# arrayboard_r0a.net
KiCad netlist of a schematic drawn in EAGLE
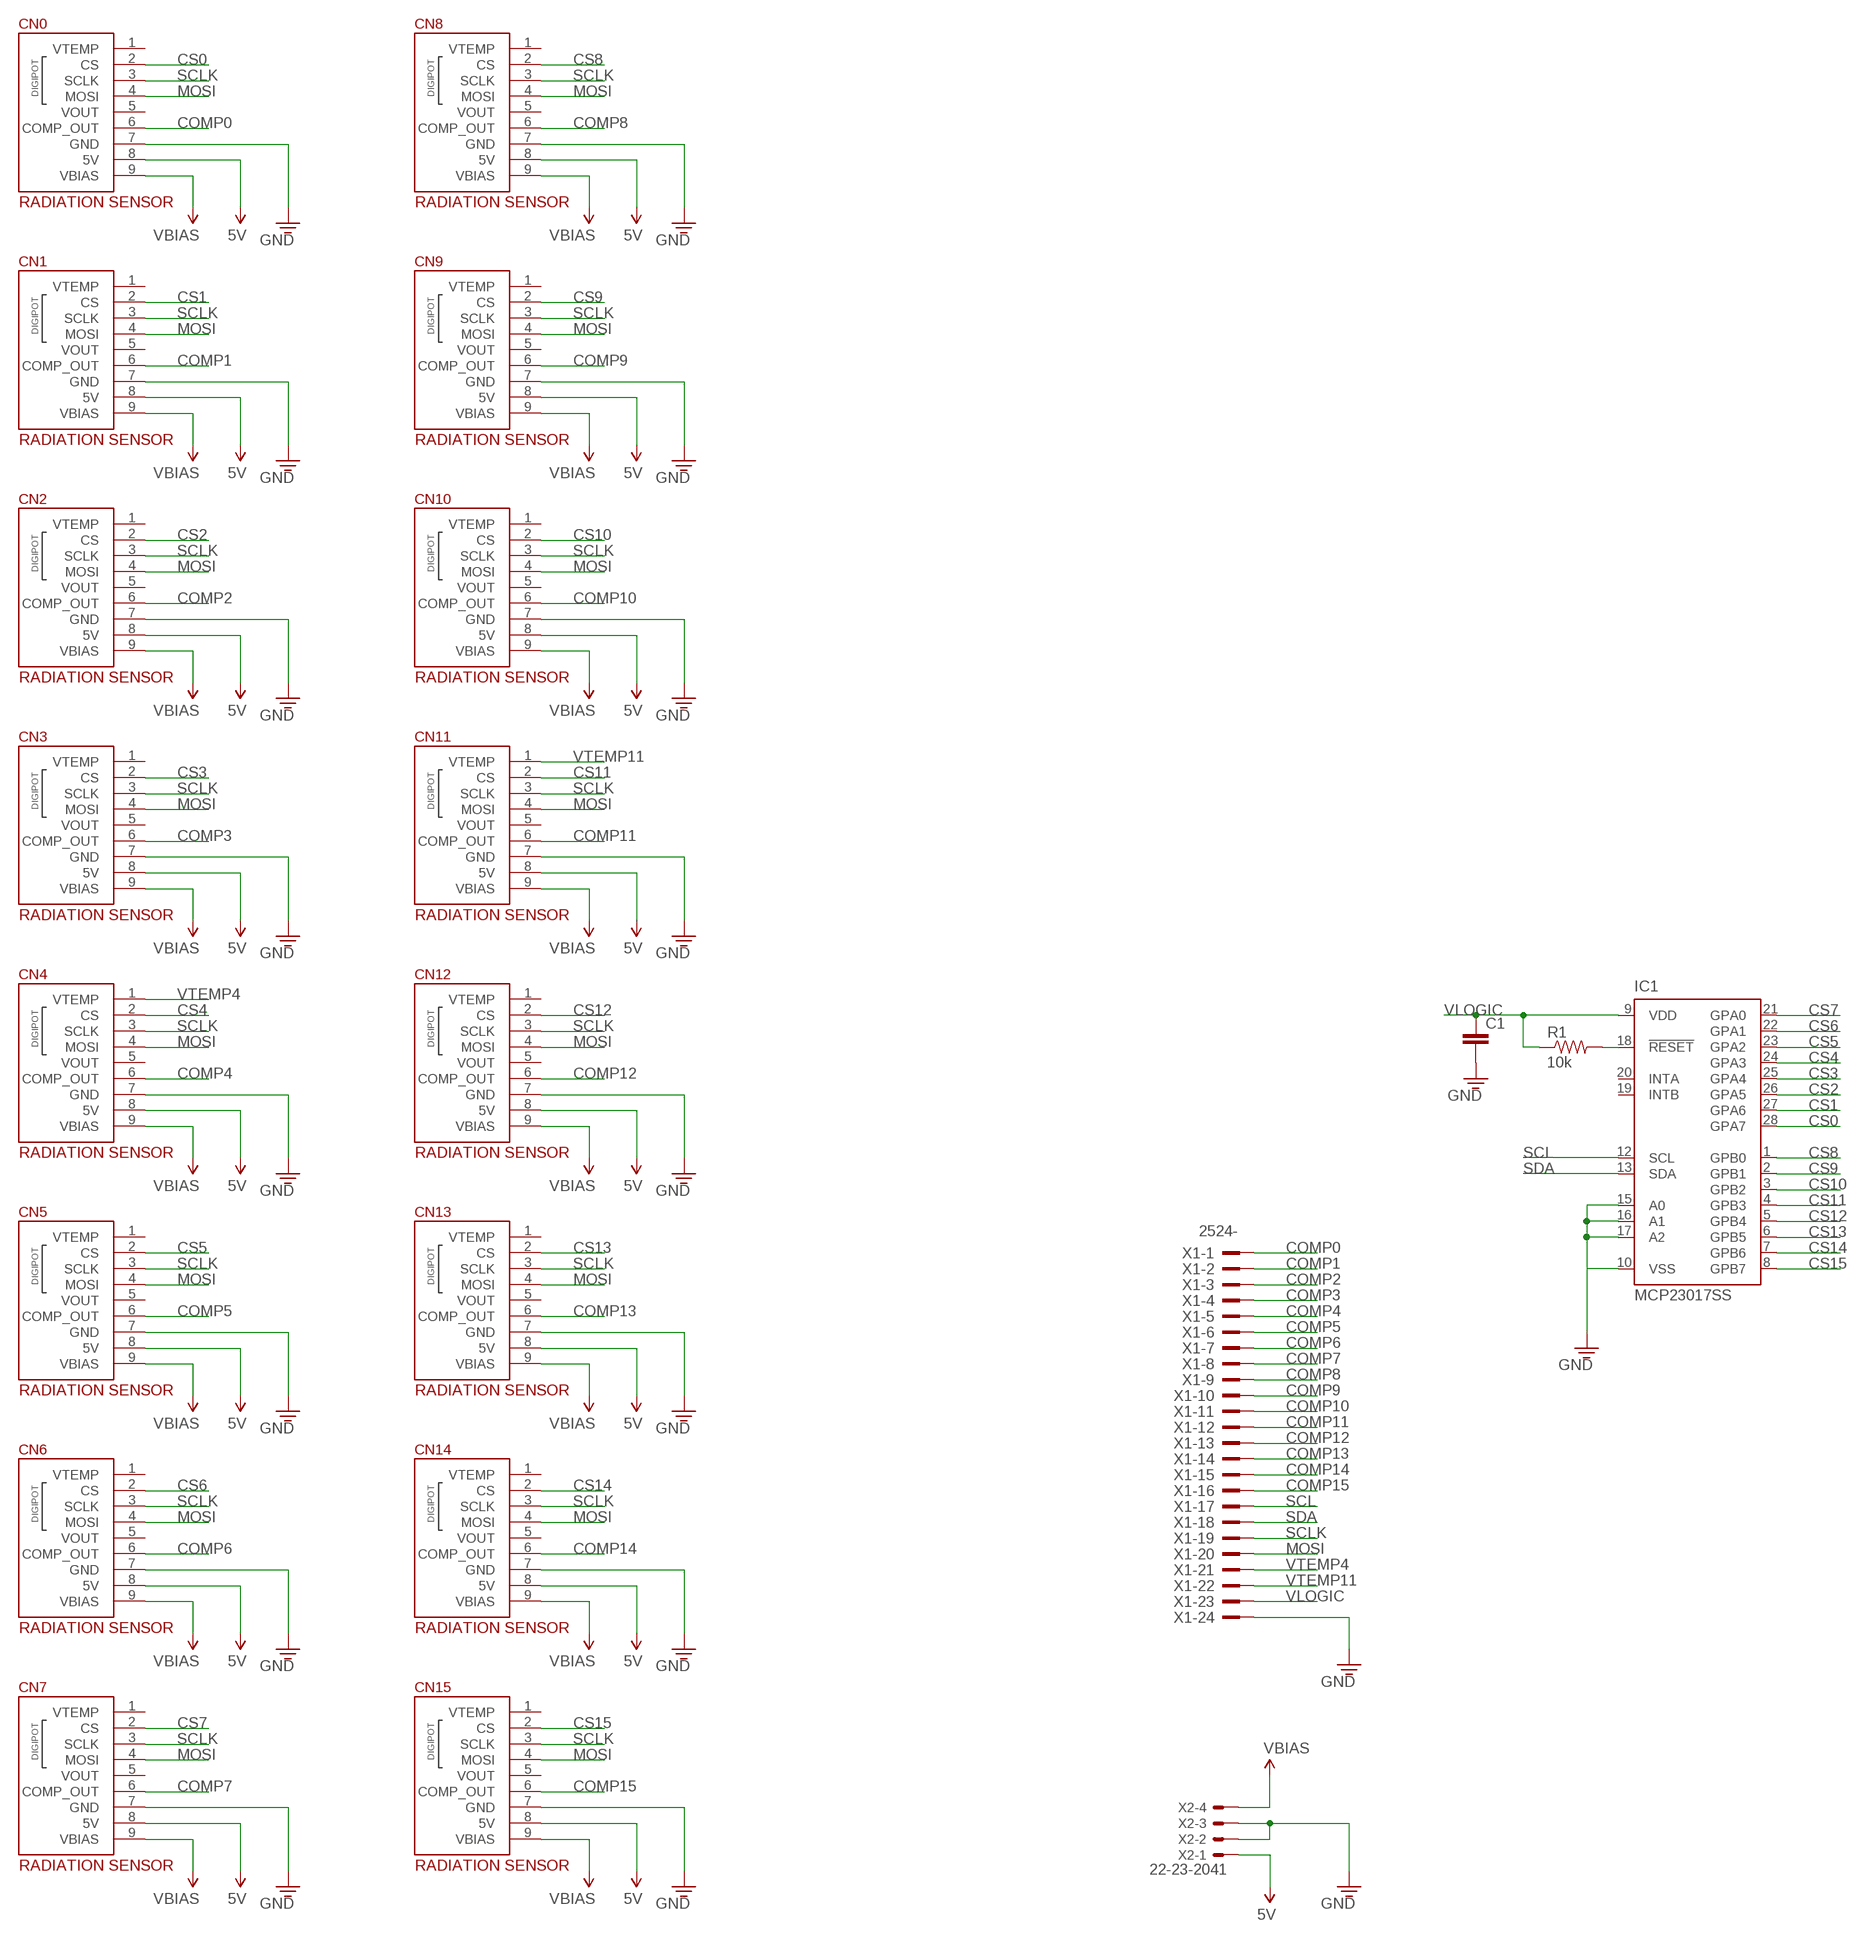
[diagram p0: schematic, sheet 1]

(export (version "E")
  (design (tool "Eeschema 10.0.6"))
  (components
    (comp (ref "C1")
      (value "CAP0603")
      (footprint "eagle-import:0603")
      (libsource (lib "eagle-import") (part "CAP0603"))
    )
    (comp (ref "CN0")
      (value "RADIATION-SENSOR-REV1")
      (footprint "eagle-import:RADIATION-SENSOR-REV1")
      (libsource (lib "eagle-import") (part "RADIATION-SENSOR-REV1"))
    )
    (comp (ref "CN1")
      (value "RADIATION-SENSOR-REV1")
      (footprint "eagle-import:RADIATION-SENSOR-REV1")
      (libsource (lib "eagle-import") (part "RADIATION-SENSOR-REV1"))
    )
    (comp (ref "CN2")
      (value "RADIATION-SENSOR-REV1")
      (footprint "eagle-import:RADIATION-SENSOR-REV1")
      (libsource (lib "eagle-import") (part "RADIATION-SENSOR-REV1"))
    )
    (comp (ref "CN3")
      (value "RADIATION-SENSOR-REV1")
      (footprint "eagle-import:RADIATION-SENSOR-REV1")
      (libsource (lib "eagle-import") (part "RADIATION-SENSOR-REV1"))
    )
    (comp (ref "CN4")
      (value "RADIATION-SENSOR-REV1")
      (footprint "eagle-import:RADIATION-SENSOR-REV1")
      (libsource (lib "eagle-import") (part "RADIATION-SENSOR-REV1"))
    )
    (comp (ref "CN5")
      (value "RADIATION-SENSOR-REV1")
      (footprint "eagle-import:RADIATION-SENSOR-REV1")
      (libsource (lib "eagle-import") (part "RADIATION-SENSOR-REV1"))
    )
    (comp (ref "CN6")
      (value "RADIATION-SENSOR-REV1")
      (footprint "eagle-import:RADIATION-SENSOR-REV1")
      (libsource (lib "eagle-import") (part "RADIATION-SENSOR-REV1"))
    )
    (comp (ref "CN7")
      (value "RADIATION-SENSOR-REV1")
      (footprint "eagle-import:RADIATION-SENSOR-REV1")
      (libsource (lib "eagle-import") (part "RADIATION-SENSOR-REV1"))
    )
    (comp (ref "CN8")
      (value "RADIATION-SENSOR-REV1")
      (footprint "eagle-import:RADIATION-SENSOR-REV1")
      (libsource (lib "eagle-import") (part "RADIATION-SENSOR-REV1"))
    )
    (comp (ref "CN9")
      (value "RADIATION-SENSOR-REV1")
      (footprint "eagle-import:RADIATION-SENSOR-REV1")
      (libsource (lib "eagle-import") (part "RADIATION-SENSOR-REV1"))
    )
    (comp (ref "CN10")
      (value "RADIATION-SENSOR-REV1")
      (footprint "eagle-import:RADIATION-SENSOR-REV1")
      (libsource (lib "eagle-import") (part "RADIATION-SENSOR-REV1"))
    )
    (comp (ref "CN11")
      (value "RADIATION-SENSOR-REV1")
      (footprint "eagle-import:RADIATION-SENSOR-REV1")
      (libsource (lib "eagle-import") (part "RADIATION-SENSOR-REV1"))
    )
    (comp (ref "CN12")
      (value "RADIATION-SENSOR-REV1")
      (footprint "eagle-import:RADIATION-SENSOR-REV1")
      (libsource (lib "eagle-import") (part "RADIATION-SENSOR-REV1"))
    )
    (comp (ref "CN13")
      (value "RADIATION-SENSOR-REV1")
      (footprint "eagle-import:RADIATION-SENSOR-REV1")
      (libsource (lib "eagle-import") (part "RADIATION-SENSOR-REV1"))
    )
    (comp (ref "CN14")
      (value "RADIATION-SENSOR-REV1")
      (footprint "eagle-import:RADIATION-SENSOR-REV1")
      (libsource (lib "eagle-import") (part "RADIATION-SENSOR-REV1"))
    )
    (comp (ref "CN15")
      (value "RADIATION-SENSOR-REV1")
      (footprint "eagle-import:RADIATION-SENSOR-REV1")
      (libsource (lib "eagle-import") (part "RADIATION-SENSOR-REV1"))
    )
    (comp (ref "IC1")
      (value "MCP23017SS")
      (footprint "eagle-import:SSOP28")
      (libsource (lib "eagle-import") (part "MCP23017SS"))
    )
    (comp (ref "R1")
      (value "10k")
      (footprint "eagle-import:0603")
      (libsource (lib "eagle-import") (part "RESISTOR0603"))
    )
    (comp (ref "X1")
      (value "2524-")
      (footprint "eagle-import:PAK100_2500-24")
      (libsource (lib "eagle-import") (part "2524-"))
    )
    (comp (ref "X2")
      (value "22-23-2041")
      (footprint "eagle-import:22-23-2041")
      (fields (field (name "MF") "MOLEX"))
      (libsource (lib "eagle-import") (part "22-23-2041"))
    )
  )
  (nets
    (net (code "1") (name "/COMP0") (class "Default")
      (node (ref "CN0") (pin "6") (pinfunction "COMP_OUT_6") (pintype "bidirectional"))
      (node (ref "X1") (pin "1") (pinfunction "KL_1") (pintype "passive"))
    )
    (net (code "2") (name "/COMP1") (class "Default")
      (node (ref "CN1") (pin "6") (pinfunction "COMP_OUT_6") (pintype "bidirectional"))
      (node (ref "X1") (pin "2") (pinfunction "KL_2") (pintype "passive"))
    )
    (net (code "3") (name "/COMP2") (class "Default")
      (node (ref "CN2") (pin "6") (pinfunction "COMP_OUT_6") (pintype "bidirectional"))
      (node (ref "X1") (pin "3") (pinfunction "KL_3") (pintype "passive"))
    )
    (net (code "4") (name "/COMP3") (class "Default")
      (node (ref "CN3") (pin "6") (pinfunction "COMP_OUT_6") (pintype "bidirectional"))
      (node (ref "X1") (pin "4") (pinfunction "KL_4") (pintype "passive"))
    )
    (net (code "5") (name "/COMP4") (class "Default")
      (node (ref "CN4") (pin "6") (pinfunction "COMP_OUT_6") (pintype "bidirectional"))
      (node (ref "X1") (pin "5") (pinfunction "KL_5") (pintype "passive"))
    )
    (net (code "6") (name "/COMP5") (class "Default")
      (node (ref "CN5") (pin "6") (pinfunction "COMP_OUT_6") (pintype "bidirectional"))
      (node (ref "X1") (pin "6") (pinfunction "KL_6") (pintype "passive"))
    )
    (net (code "7") (name "/COMP6") (class "Default")
      (node (ref "CN6") (pin "6") (pinfunction "COMP_OUT_6") (pintype "bidirectional"))
      (node (ref "X1") (pin "7") (pinfunction "KL_7") (pintype "passive"))
    )
    (net (code "8") (name "/COMP7") (class "Default")
      (node (ref "CN7") (pin "6") (pinfunction "COMP_OUT_6") (pintype "bidirectional"))
      (node (ref "X1") (pin "8") (pinfunction "KL_8") (pintype "passive"))
    )
    (net (code "9") (name "/COMP8") (class "Default")
      (node (ref "CN8") (pin "6") (pinfunction "COMP_OUT_6") (pintype "bidirectional"))
      (node (ref "X1") (pin "9") (pinfunction "KL_9") (pintype "passive"))
    )
    (net (code "10") (name "/COMP9") (class "Default")
      (node (ref "CN9") (pin "6") (pinfunction "COMP_OUT_6") (pintype "bidirectional"))
      (node (ref "X1") (pin "10") (pinfunction "KL_10") (pintype "passive"))
    )
    (net (code "11") (name "/COMP10") (class "Default")
      (node (ref "CN10") (pin "6") (pinfunction "COMP_OUT_6") (pintype "bidirectional"))
      (node (ref "X1") (pin "11") (pinfunction "KL_11") (pintype "passive"))
    )
    (net (code "12") (name "/COMP11") (class "Default")
      (node (ref "CN11") (pin "6") (pinfunction "COMP_OUT_6") (pintype "bidirectional"))
      (node (ref "X1") (pin "12") (pinfunction "KL_12") (pintype "passive"))
    )
    (net (code "13") (name "/COMP12") (class "Default")
      (node (ref "CN12") (pin "6") (pinfunction "COMP_OUT_6") (pintype "bidirectional"))
      (node (ref "X1") (pin "13") (pinfunction "KL_13") (pintype "passive"))
    )
    (net (code "14") (name "/COMP13") (class "Default")
      (node (ref "CN13") (pin "6") (pinfunction "COMP_OUT_6") (pintype "bidirectional"))
      (node (ref "X1") (pin "14") (pinfunction "KL_14") (pintype "passive"))
    )
    (net (code "15") (name "/COMP14") (class "Default")
      (node (ref "CN14") (pin "6") (pinfunction "COMP_OUT_6") (pintype "bidirectional"))
      (node (ref "X1") (pin "15") (pinfunction "KL_15") (pintype "passive"))
    )
    (net (code "16") (name "/COMP15") (class "Default")
      (node (ref "CN15") (pin "6") (pinfunction "COMP_OUT_6") (pintype "bidirectional"))
      (node (ref "X1") (pin "16") (pinfunction "KL_16") (pintype "passive"))
    )
    (net (code "17") (name "/CS0") (class "Default")
      (node (ref "CN0") (pin "2") (pinfunction "CS_2") (pintype "bidirectional"))
      (node (ref "IC1") (pin "28") (pinfunction "GPA7_28") (pintype "bidirectional"))
    )
    (net (code "18") (name "/CS1") (class "Default")
      (node (ref "CN1") (pin "2") (pinfunction "CS_2") (pintype "bidirectional"))
      (node (ref "IC1") (pin "27") (pinfunction "GPA6_27") (pintype "bidirectional"))
    )
    (net (code "19") (name "/CS2") (class "Default")
      (node (ref "CN2") (pin "2") (pinfunction "CS_2") (pintype "bidirectional"))
      (node (ref "IC1") (pin "26") (pinfunction "GPA5_26") (pintype "bidirectional"))
    )
    (net (code "20") (name "/CS3") (class "Default")
      (node (ref "CN3") (pin "2") (pinfunction "CS_2") (pintype "bidirectional"))
      (node (ref "IC1") (pin "25") (pinfunction "GPA4_25") (pintype "bidirectional"))
    )
    (net (code "21") (name "/CS4") (class "Default")
      (node (ref "CN4") (pin "2") (pinfunction "CS_2") (pintype "bidirectional"))
      (node (ref "IC1") (pin "24") (pinfunction "GPA3_24") (pintype "bidirectional"))
    )
    (net (code "22") (name "/CS5") (class "Default")
      (node (ref "CN5") (pin "2") (pinfunction "CS_2") (pintype "bidirectional"))
      (node (ref "IC1") (pin "23") (pinfunction "GPA2_23") (pintype "bidirectional"))
    )
    (net (code "23") (name "/CS6") (class "Default")
      (node (ref "CN6") (pin "2") (pinfunction "CS_2") (pintype "bidirectional"))
      (node (ref "IC1") (pin "22") (pinfunction "GPA1_22") (pintype "bidirectional"))
    )
    (net (code "24") (name "/CS7") (class "Default")
      (node (ref "CN7") (pin "2") (pinfunction "CS_2") (pintype "bidirectional"))
      (node (ref "IC1") (pin "21") (pinfunction "GPA0_21") (pintype "bidirectional"))
    )
    (net (code "25") (name "/CS8") (class "Default")
      (node (ref "CN8") (pin "2") (pinfunction "CS_2") (pintype "bidirectional"))
      (node (ref "IC1") (pin "1") (pinfunction "GPB0_1") (pintype "bidirectional"))
    )
    (net (code "26") (name "/CS9") (class "Default")
      (node (ref "CN9") (pin "2") (pinfunction "CS_2") (pintype "bidirectional"))
      (node (ref "IC1") (pin "2") (pinfunction "GPB1_2") (pintype "bidirectional"))
    )
    (net (code "27") (name "/CS10") (class "Default")
      (node (ref "CN10") (pin "2") (pinfunction "CS_2") (pintype "bidirectional"))
      (node (ref "IC1") (pin "3") (pinfunction "GPB2_3") (pintype "bidirectional"))
    )
    (net (code "28") (name "/CS11") (class "Default")
      (node (ref "CN11") (pin "2") (pinfunction "CS_2") (pintype "bidirectional"))
      (node (ref "IC1") (pin "4") (pinfunction "GPB3_4") (pintype "bidirectional"))
    )
    (net (code "29") (name "/CS12") (class "Default")
      (node (ref "CN12") (pin "2") (pinfunction "CS_2") (pintype "bidirectional"))
      (node (ref "IC1") (pin "5") (pinfunction "GPB4_5") (pintype "bidirectional"))
    )
    (net (code "30") (name "/CS13") (class "Default")
      (node (ref "CN13") (pin "2") (pinfunction "CS_2") (pintype "bidirectional"))
      (node (ref "IC1") (pin "6") (pinfunction "GPB5_6") (pintype "bidirectional"))
    )
    (net (code "31") (name "/CS14") (class "Default")
      (node (ref "CN14") (pin "2") (pinfunction "CS_2") (pintype "bidirectional"))
      (node (ref "IC1") (pin "7") (pinfunction "GPB6_7") (pintype "bidirectional"))
    )
    (net (code "32") (name "/CS15") (class "Default")
      (node (ref "CN15") (pin "2") (pinfunction "CS_2") (pintype "bidirectional"))
      (node (ref "IC1") (pin "8") (pinfunction "GPB7_8") (pintype "bidirectional"))
    )
    (net (code "33") (name "/MOSI") (class "Default")
      (node (ref "CN0") (pin "4") (pinfunction "MOSI_4") (pintype "bidirectional"))
      (node (ref "CN1") (pin "4") (pinfunction "MOSI_4") (pintype "bidirectional"))
      (node (ref "CN10") (pin "4") (pinfunction "MOSI_4") (pintype "bidirectional"))
      (node (ref "CN11") (pin "4") (pinfunction "MOSI_4") (pintype "bidirectional"))
      (node (ref "CN12") (pin "4") (pinfunction "MOSI_4") (pintype "bidirectional"))
      (node (ref "CN13") (pin "4") (pinfunction "MOSI_4") (pintype "bidirectional"))
      (node (ref "CN14") (pin "4") (pinfunction "MOSI_4") (pintype "bidirectional"))
      (node (ref "CN15") (pin "4") (pinfunction "MOSI_4") (pintype "bidirectional"))
      (node (ref "CN2") (pin "4") (pinfunction "MOSI_4") (pintype "bidirectional"))
      (node (ref "CN3") (pin "4") (pinfunction "MOSI_4") (pintype "bidirectional"))
      (node (ref "CN4") (pin "4") (pinfunction "MOSI_4") (pintype "bidirectional"))
      (node (ref "CN5") (pin "4") (pinfunction "MOSI_4") (pintype "bidirectional"))
      (node (ref "CN6") (pin "4") (pinfunction "MOSI_4") (pintype "bidirectional"))
      (node (ref "CN7") (pin "4") (pinfunction "MOSI_4") (pintype "bidirectional"))
      (node (ref "CN8") (pin "4") (pinfunction "MOSI_4") (pintype "bidirectional"))
      (node (ref "CN9") (pin "4") (pinfunction "MOSI_4") (pintype "bidirectional"))
      (node (ref "X1") (pin "20") (pinfunction "KL_20") (pintype "passive"))
    )
    (net (code "34") (name "/SCL") (class "Default")
      (node (ref "IC1") (pin "12") (pinfunction "SCL_12") (pintype "input"))
      (node (ref "X1") (pin "17") (pinfunction "KL_17") (pintype "passive"))
    )
    (net (code "35") (name "/SCLK") (class "Default")
      (node (ref "CN0") (pin "3") (pinfunction "SCLK_3") (pintype "bidirectional"))
      (node (ref "CN1") (pin "3") (pinfunction "SCLK_3") (pintype "bidirectional"))
      (node (ref "CN10") (pin "3") (pinfunction "SCLK_3") (pintype "bidirectional"))
      (node (ref "CN11") (pin "3") (pinfunction "SCLK_3") (pintype "bidirectional"))
      (node (ref "CN12") (pin "3") (pinfunction "SCLK_3") (pintype "bidirectional"))
      (node (ref "CN13") (pin "3") (pinfunction "SCLK_3") (pintype "bidirectional"))
      (node (ref "CN14") (pin "3") (pinfunction "SCLK_3") (pintype "bidirectional"))
      (node (ref "CN15") (pin "3") (pinfunction "SCLK_3") (pintype "bidirectional"))
      (node (ref "CN2") (pin "3") (pinfunction "SCLK_3") (pintype "bidirectional"))
      (node (ref "CN3") (pin "3") (pinfunction "SCLK_3") (pintype "bidirectional"))
      (node (ref "CN4") (pin "3") (pinfunction "SCLK_3") (pintype "bidirectional"))
      (node (ref "CN5") (pin "3") (pinfunction "SCLK_3") (pintype "bidirectional"))
      (node (ref "CN6") (pin "3") (pinfunction "SCLK_3") (pintype "bidirectional"))
      (node (ref "CN7") (pin "3") (pinfunction "SCLK_3") (pintype "bidirectional"))
      (node (ref "CN8") (pin "3") (pinfunction "SCLK_3") (pintype "bidirectional"))
      (node (ref "CN9") (pin "3") (pinfunction "SCLK_3") (pintype "bidirectional"))
      (node (ref "X1") (pin "19") (pinfunction "KL_19") (pintype "passive"))
    )
    (net (code "36") (name "/SDA") (class "Default")
      (node (ref "IC1") (pin "13") (pinfunction "SDA_13") (pintype "bidirectional"))
      (node (ref "X1") (pin "18") (pinfunction "KL_18") (pintype "passive"))
    )
    (net (code "37") (name "/VLOGIC") (class "Default")
      (node (ref "C1") (pin "1") (pinfunction "1_1") (pintype "passive"))
      (node (ref "IC1") (pin "9") (pinfunction "VDD_9") (pintype "power_in"))
      (node (ref "R1") (pin "1") (pinfunction "1_1") (pintype "passive"))
      (node (ref "X1") (pin "23") (pinfunction "KL_23") (pintype "passive"))
    )
    (net (code "38") (name "/VTEMP4") (class "Default")
      (node (ref "CN4") (pin "1") (pinfunction "VTEMP_1") (pintype "bidirectional"))
      (node (ref "X1") (pin "21") (pinfunction "KL_21") (pintype "passive"))
    )
    (net (code "39") (name "/VTEMP11") (class "Default")
      (node (ref "CN11") (pin "1") (pinfunction "VTEMP_1") (pintype "bidirectional"))
      (node (ref "X1") (pin "22") (pinfunction "KL_22") (pintype "passive"))
    )
    (net (code "40") (name "5V") (class "Default")
      (node (ref "CN0") (pin "8") (pinfunction "5V_8") (pintype "bidirectional"))
      (node (ref "CN1") (pin "8") (pinfunction "5V_8") (pintype "bidirectional"))
      (node (ref "CN10") (pin "8") (pinfunction "5V_8") (pintype "bidirectional"))
      (node (ref "CN11") (pin "8") (pinfunction "5V_8") (pintype "bidirectional"))
      (node (ref "CN12") (pin "8") (pinfunction "5V_8") (pintype "bidirectional"))
      (node (ref "CN13") (pin "8") (pinfunction "5V_8") (pintype "bidirectional"))
      (node (ref "CN14") (pin "8") (pinfunction "5V_8") (pintype "bidirectional"))
      (node (ref "CN15") (pin "8") (pinfunction "5V_8") (pintype "bidirectional"))
      (node (ref "CN2") (pin "8") (pinfunction "5V_8") (pintype "bidirectional"))
      (node (ref "CN3") (pin "8") (pinfunction "5V_8") (pintype "bidirectional"))
      (node (ref "CN4") (pin "8") (pinfunction "5V_8") (pintype "bidirectional"))
      (node (ref "CN5") (pin "8") (pinfunction "5V_8") (pintype "bidirectional"))
      (node (ref "CN6") (pin "8") (pinfunction "5V_8") (pintype "bidirectional"))
      (node (ref "CN7") (pin "8") (pinfunction "5V_8") (pintype "bidirectional"))
      (node (ref "CN8") (pin "8") (pinfunction "5V_8") (pintype "bidirectional"))
      (node (ref "CN9") (pin "8") (pinfunction "5V_8") (pintype "bidirectional"))
      (node (ref "X2") (pin "1") (pinfunction "S_1") (pintype "passive"))
    )
    (net (code "41") (name "GND") (class "Default")
      (node (ref "C1") (pin "2") (pinfunction "2_2") (pintype "passive"))
      (node (ref "CN0") (pin "7") (pinfunction "GND_7") (pintype "bidirectional"))
      (node (ref "CN1") (pin "7") (pinfunction "GND_7") (pintype "bidirectional"))
      (node (ref "CN10") (pin "7") (pinfunction "GND_7") (pintype "bidirectional"))
      (node (ref "CN11") (pin "7") (pinfunction "GND_7") (pintype "bidirectional"))
      (node (ref "CN12") (pin "7") (pinfunction "GND_7") (pintype "bidirectional"))
      (node (ref "CN13") (pin "7") (pinfunction "GND_7") (pintype "bidirectional"))
      (node (ref "CN14") (pin "7") (pinfunction "GND_7") (pintype "bidirectional"))
      (node (ref "CN15") (pin "7") (pinfunction "GND_7") (pintype "bidirectional"))
      (node (ref "CN2") (pin "7") (pinfunction "GND_7") (pintype "bidirectional"))
      (node (ref "CN3") (pin "7") (pinfunction "GND_7") (pintype "bidirectional"))
      (node (ref "CN4") (pin "7") (pinfunction "GND_7") (pintype "bidirectional"))
      (node (ref "CN5") (pin "7") (pinfunction "GND_7") (pintype "bidirectional"))
      (node (ref "CN6") (pin "7") (pinfunction "GND_7") (pintype "bidirectional"))
      (node (ref "CN7") (pin "7") (pinfunction "GND_7") (pintype "bidirectional"))
      (node (ref "CN8") (pin "7") (pinfunction "GND_7") (pintype "bidirectional"))
      (node (ref "CN9") (pin "7") (pinfunction "GND_7") (pintype "bidirectional"))
      (node (ref "IC1") (pin "10") (pinfunction "VSS_10") (pintype "power_in"))
      (node (ref "IC1") (pin "15") (pinfunction "A0_15") (pintype "input"))
      (node (ref "IC1") (pin "16") (pinfunction "A1_16") (pintype "input"))
      (node (ref "IC1") (pin "17") (pinfunction "A2_17") (pintype "input"))
      (node (ref "X1") (pin "24") (pinfunction "KL_24") (pintype "passive"))
      (node (ref "X2") (pin "2") (pinfunction "S_2") (pintype "passive"))
      (node (ref "X2") (pin "3") (pinfunction "S_3") (pintype "passive"))
    )
    (net (code "42") (name "Net-(IC1-~{RESET})") (class "Default")
      (node (ref "IC1") (pin "18") (pinfunction "~{RESET}_18") (pintype "input"))
      (node (ref "R1") (pin "2") (pinfunction "2_2") (pintype "passive"))
    )
    (net (code "43") (name "VBIAS") (class "Default")
      (node (ref "CN0") (pin "9") (pinfunction "VBIAS_9") (pintype "bidirectional"))
      (node (ref "CN1") (pin "9") (pinfunction "VBIAS_9") (pintype "bidirectional"))
      (node (ref "CN10") (pin "9") (pinfunction "VBIAS_9") (pintype "bidirectional"))
      (node (ref "CN11") (pin "9") (pinfunction "VBIAS_9") (pintype "bidirectional"))
      (node (ref "CN12") (pin "9") (pinfunction "VBIAS_9") (pintype "bidirectional"))
      (node (ref "CN13") (pin "9") (pinfunction "VBIAS_9") (pintype "bidirectional"))
      (node (ref "CN14") (pin "9") (pinfunction "VBIAS_9") (pintype "bidirectional"))
      (node (ref "CN15") (pin "9") (pinfunction "VBIAS_9") (pintype "bidirectional"))
      (node (ref "CN2") (pin "9") (pinfunction "VBIAS_9") (pintype "bidirectional"))
      (node (ref "CN3") (pin "9") (pinfunction "VBIAS_9") (pintype "bidirectional"))
      (node (ref "CN4") (pin "9") (pinfunction "VBIAS_9") (pintype "bidirectional"))
      (node (ref "CN5") (pin "9") (pinfunction "VBIAS_9") (pintype "bidirectional"))
      (node (ref "CN6") (pin "9") (pinfunction "VBIAS_9") (pintype "bidirectional"))
      (node (ref "CN7") (pin "9") (pinfunction "VBIAS_9") (pintype "bidirectional"))
      (node (ref "CN8") (pin "9") (pinfunction "VBIAS_9") (pintype "bidirectional"))
      (node (ref "CN9") (pin "9") (pinfunction "VBIAS_9") (pintype "bidirectional"))
      (node (ref "X2") (pin "4") (pinfunction "S_4") (pintype "passive"))
    )
    (net (code "44") (name "unconnected-(CN0-VOUT-Pad5)") (class "Default")
      (node (ref "CN0") (pin "5") (pinfunction "VOUT_5") (pintype "bidirectional"))
    )
    (net (code "45") (name "unconnected-(CN0-VTEMP-Pad1)") (class "Default")
      (node (ref "CN0") (pin "1") (pinfunction "VTEMP_1") (pintype "bidirectional"))
    )
    (net (code "46") (name "unconnected-(CN1-VOUT-Pad5)") (class "Default")
      (node (ref "CN1") (pin "5") (pinfunction "VOUT_5") (pintype "bidirectional"))
    )
    (net (code "47") (name "unconnected-(CN1-VTEMP-Pad1)") (class "Default")
      (node (ref "CN1") (pin "1") (pinfunction "VTEMP_1") (pintype "bidirectional"))
    )
    (net (code "48") (name "unconnected-(CN2-VOUT-Pad5)") (class "Default")
      (node (ref "CN2") (pin "5") (pinfunction "VOUT_5") (pintype "bidirectional"))
    )
    (net (code "49") (name "unconnected-(CN2-VTEMP-Pad1)") (class "Default")
      (node (ref "CN2") (pin "1") (pinfunction "VTEMP_1") (pintype "bidirectional"))
    )
    (net (code "50") (name "unconnected-(CN3-VOUT-Pad5)") (class "Default")
      (node (ref "CN3") (pin "5") (pinfunction "VOUT_5") (pintype "bidirectional"))
    )
    (net (code "51") (name "unconnected-(CN3-VTEMP-Pad1)") (class "Default")
      (node (ref "CN3") (pin "1") (pinfunction "VTEMP_1") (pintype "bidirectional"))
    )
    (net (code "52") (name "unconnected-(CN4-VOUT-Pad5)") (class "Default")
      (node (ref "CN4") (pin "5") (pinfunction "VOUT_5") (pintype "bidirectional"))
    )
    (net (code "53") (name "unconnected-(CN5-VOUT-Pad5)") (class "Default")
      (node (ref "CN5") (pin "5") (pinfunction "VOUT_5") (pintype "bidirectional"))
    )
    (net (code "54") (name "unconnected-(CN5-VTEMP-Pad1)") (class "Default")
      (node (ref "CN5") (pin "1") (pinfunction "VTEMP_1") (pintype "bidirectional"))
    )
    (net (code "55") (name "unconnected-(CN6-VOUT-Pad5)") (class "Default")
      (node (ref "CN6") (pin "5") (pinfunction "VOUT_5") (pintype "bidirectional"))
    )
    (net (code "56") (name "unconnected-(CN6-VTEMP-Pad1)") (class "Default")
      (node (ref "CN6") (pin "1") (pinfunction "VTEMP_1") (pintype "bidirectional"))
    )
    (net (code "57") (name "unconnected-(CN7-VOUT-Pad5)") (class "Default")
      (node (ref "CN7") (pin "5") (pinfunction "VOUT_5") (pintype "bidirectional"))
    )
    (net (code "58") (name "unconnected-(CN7-VTEMP-Pad1)") (class "Default")
      (node (ref "CN7") (pin "1") (pinfunction "VTEMP_1") (pintype "bidirectional"))
    )
    (net (code "59") (name "unconnected-(CN8-VOUT-Pad5)") (class "Default")
      (node (ref "CN8") (pin "5") (pinfunction "VOUT_5") (pintype "bidirectional"))
    )
    (net (code "60") (name "unconnected-(CN8-VTEMP-Pad1)") (class "Default")
      (node (ref "CN8") (pin "1") (pinfunction "VTEMP_1") (pintype "bidirectional"))
    )
    (net (code "61") (name "unconnected-(CN9-VOUT-Pad5)") (class "Default")
      (node (ref "CN9") (pin "5") (pinfunction "VOUT_5") (pintype "bidirectional"))
    )
    (net (code "62") (name "unconnected-(CN9-VTEMP-Pad1)") (class "Default")
      (node (ref "CN9") (pin "1") (pinfunction "VTEMP_1") (pintype "bidirectional"))
    )
    (net (code "63") (name "unconnected-(CN10-VOUT-Pad5)") (class "Default")
      (node (ref "CN10") (pin "5") (pinfunction "VOUT_5") (pintype "bidirectional"))
    )
    (net (code "64") (name "unconnected-(CN10-VTEMP-Pad1)") (class "Default")
      (node (ref "CN10") (pin "1") (pinfunction "VTEMP_1") (pintype "bidirectional"))
    )
    (net (code "65") (name "unconnected-(CN11-VOUT-Pad5)") (class "Default")
      (node (ref "CN11") (pin "5") (pinfunction "VOUT_5") (pintype "bidirectional"))
    )
    (net (code "66") (name "unconnected-(CN12-VOUT-Pad5)") (class "Default")
      (node (ref "CN12") (pin "5") (pinfunction "VOUT_5") (pintype "bidirectional"))
    )
    (net (code "67") (name "unconnected-(CN12-VTEMP-Pad1)") (class "Default")
      (node (ref "CN12") (pin "1") (pinfunction "VTEMP_1") (pintype "bidirectional"))
    )
    (net (code "68") (name "unconnected-(CN13-VOUT-Pad5)") (class "Default")
      (node (ref "CN13") (pin "5") (pinfunction "VOUT_5") (pintype "bidirectional"))
    )
    (net (code "69") (name "unconnected-(CN13-VTEMP-Pad1)") (class "Default")
      (node (ref "CN13") (pin "1") (pinfunction "VTEMP_1") (pintype "bidirectional"))
    )
    (net (code "70") (name "unconnected-(CN14-VOUT-Pad5)") (class "Default")
      (node (ref "CN14") (pin "5") (pinfunction "VOUT_5") (pintype "bidirectional"))
    )
    (net (code "71") (name "unconnected-(CN14-VTEMP-Pad1)") (class "Default")
      (node (ref "CN14") (pin "1") (pinfunction "VTEMP_1") (pintype "bidirectional"))
    )
    (net (code "72") (name "unconnected-(CN15-VOUT-Pad5)") (class "Default")
      (node (ref "CN15") (pin "5") (pinfunction "VOUT_5") (pintype "bidirectional"))
    )
    (net (code "73") (name "unconnected-(CN15-VTEMP-Pad1)") (class "Default")
      (node (ref "CN15") (pin "1") (pinfunction "VTEMP_1") (pintype "bidirectional"))
    )
    (net (code "74") (name "unconnected-(IC1-INTA-Pad20)") (class "Default")
      (node (ref "IC1") (pin "20") (pinfunction "INTA_20") (pintype "output"))
    )
    (net (code "75") (name "unconnected-(IC1-INTB-Pad19)") (class "Default")
      (node (ref "IC1") (pin "19") (pinfunction "INTB_19") (pintype "output"))
    )
  )
)
